# Sensor_HallArray_StandAlone_2mm.net
KiCad netlist of a schematic drawn in EAGLE
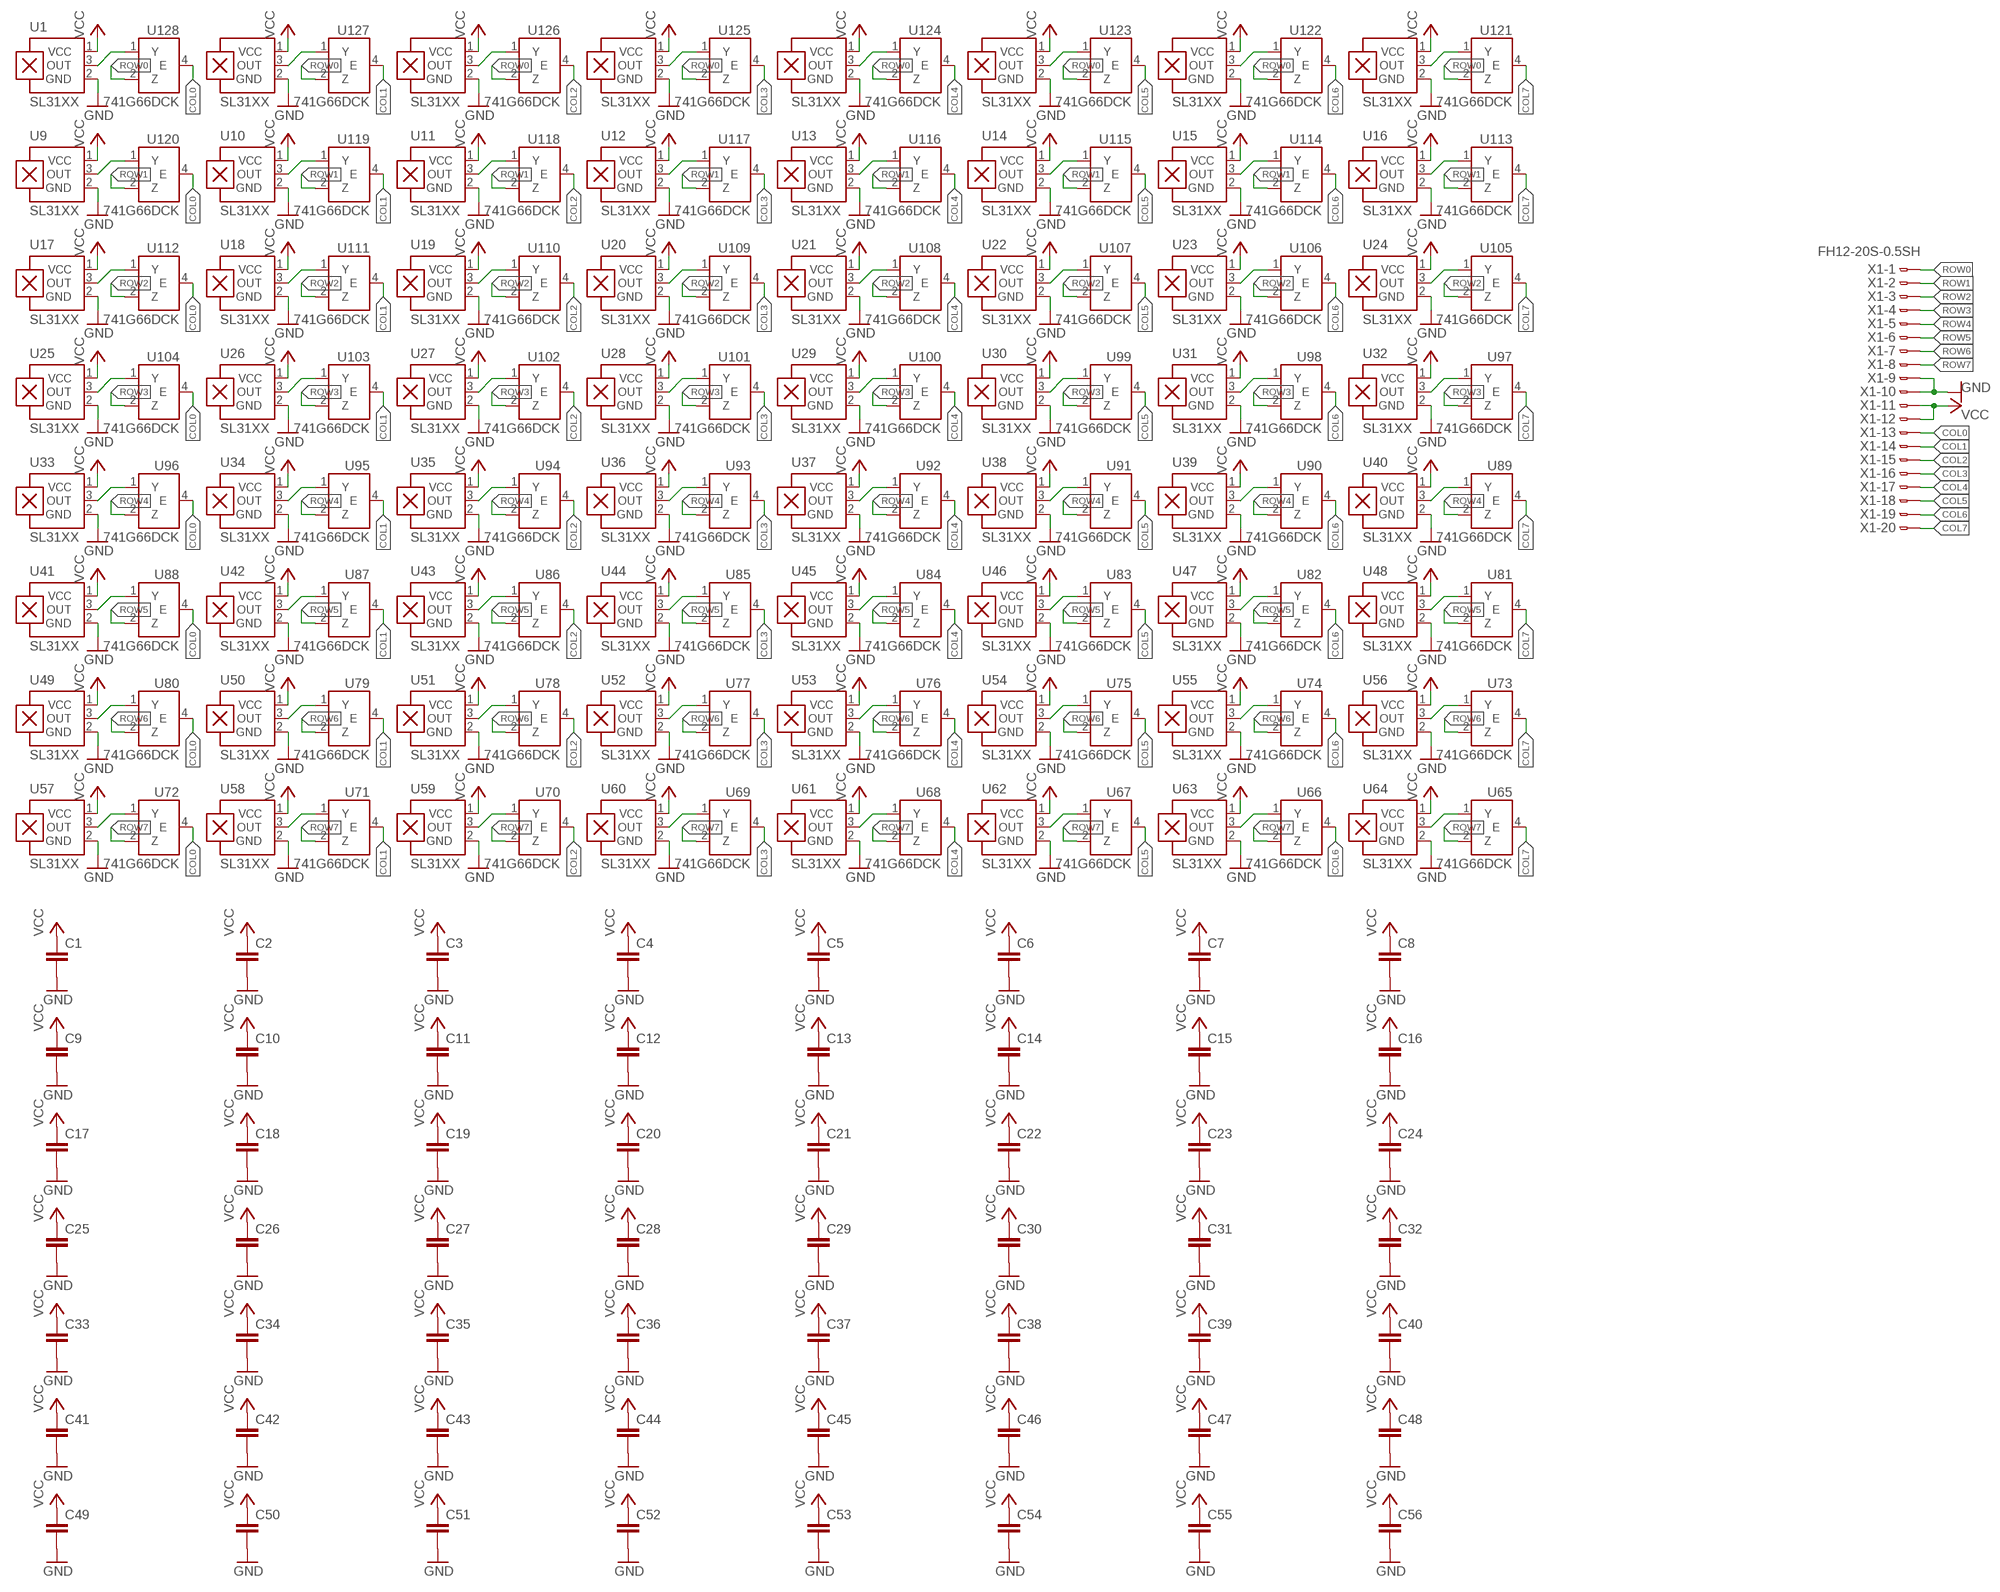
[diagram p0: schematic, sheet 1]

(export (version "E")
  (design (tool "Eeschema 10.0.6"))
  (components
    (comp (ref "C1")
      (value "C-EUC0201")
      (footprint "eagle-import:C0201")
      (libsource (lib "eagle-import") (part "C-EUC0201"))
    )
    (comp (ref "C2")
      (value "C-EUC0201")
      (footprint "eagle-import:C0201")
      (libsource (lib "eagle-import") (part "C-EUC0201"))
    )
    (comp (ref "C3")
      (value "C-EUC0201")
      (footprint "eagle-import:C0201")
      (libsource (lib "eagle-import") (part "C-EUC0201"))
    )
    (comp (ref "C4")
      (value "C-EUC0201")
      (footprint "eagle-import:C0201")
      (libsource (lib "eagle-import") (part "C-EUC0201"))
    )
    (comp (ref "C5")
      (value "C-EUC0201")
      (footprint "eagle-import:C0201")
      (libsource (lib "eagle-import") (part "C-EUC0201"))
    )
    (comp (ref "C6")
      (value "C-EUC0201")
      (footprint "eagle-import:C0201")
      (libsource (lib "eagle-import") (part "C-EUC0201"))
    )
    (comp (ref "C7")
      (value "C-EUC0201")
      (footprint "eagle-import:C0201")
      (libsource (lib "eagle-import") (part "C-EUC0201"))
    )
    (comp (ref "C8")
      (value "C-EUC0201")
      (footprint "eagle-import:C0201")
      (libsource (lib "eagle-import") (part "C-EUC0201"))
    )
    (comp (ref "C9")
      (value "C-EUC0201")
      (footprint "eagle-import:C0201")
      (libsource (lib "eagle-import") (part "C-EUC0201"))
    )
    (comp (ref "C10")
      (value "C-EUC0201")
      (footprint "eagle-import:C0201")
      (libsource (lib "eagle-import") (part "C-EUC0201"))
    )
    (comp (ref "C11")
      (value "C-EUC0201")
      (footprint "eagle-import:C0201")
      (libsource (lib "eagle-import") (part "C-EUC0201"))
    )
    (comp (ref "C12")
      (value "C-EUC0201")
      (footprint "eagle-import:C0201")
      (libsource (lib "eagle-import") (part "C-EUC0201"))
    )
    (comp (ref "C13")
      (value "C-EUC0201")
      (footprint "eagle-import:C0201")
      (libsource (lib "eagle-import") (part "C-EUC0201"))
    )
    (comp (ref "C14")
      (value "C-EUC0201")
      (footprint "eagle-import:C0201")
      (libsource (lib "eagle-import") (part "C-EUC0201"))
    )
    (comp (ref "C15")
      (value "C-EUC0201")
      (footprint "eagle-import:C0201")
      (libsource (lib "eagle-import") (part "C-EUC0201"))
    )
    (comp (ref "C16")
      (value "C-EUC0201")
      (footprint "eagle-import:C0201")
      (libsource (lib "eagle-import") (part "C-EUC0201"))
    )
    (comp (ref "C17")
      (value "C-EUC0201")
      (footprint "eagle-import:C0201")
      (libsource (lib "eagle-import") (part "C-EUC0201"))
    )
    (comp (ref "C18")
      (value "C-EUC0201")
      (footprint "eagle-import:C0201")
      (libsource (lib "eagle-import") (part "C-EUC0201"))
    )
    (comp (ref "C19")
      (value "C-EUC0201")
      (footprint "eagle-import:C0201")
      (libsource (lib "eagle-import") (part "C-EUC0201"))
    )
    (comp (ref "C20")
      (value "C-EUC0201")
      (footprint "eagle-import:C0201")
      (libsource (lib "eagle-import") (part "C-EUC0201"))
    )
    (comp (ref "C21")
      (value "C-EUC0201")
      (footprint "eagle-import:C0201")
      (libsource (lib "eagle-import") (part "C-EUC0201"))
    )
    (comp (ref "C22")
      (value "C-EUC0201")
      (footprint "eagle-import:C0201")
      (libsource (lib "eagle-import") (part "C-EUC0201"))
    )
    (comp (ref "C23")
      (value "C-EUC0201")
      (footprint "eagle-import:C0201")
      (libsource (lib "eagle-import") (part "C-EUC0201"))
    )
    (comp (ref "C24")
      (value "C-EUC0201")
      (footprint "eagle-import:C0201")
      (libsource (lib "eagle-import") (part "C-EUC0201"))
    )
    (comp (ref "C25")
      (value "C-EUC0201")
      (footprint "eagle-import:C0201")
      (libsource (lib "eagle-import") (part "C-EUC0201"))
    )
    (comp (ref "C26")
      (value "C-EUC0201")
      (footprint "eagle-import:C0201")
      (libsource (lib "eagle-import") (part "C-EUC0201"))
    )
    (comp (ref "C27")
      (value "C-EUC0201")
      (footprint "eagle-import:C0201")
      (libsource (lib "eagle-import") (part "C-EUC0201"))
    )
    (comp (ref "C28")
      (value "C-EUC0201")
      (footprint "eagle-import:C0201")
      (libsource (lib "eagle-import") (part "C-EUC0201"))
    )
    (comp (ref "C29")
      (value "C-EUC0201")
      (footprint "eagle-import:C0201")
      (libsource (lib "eagle-import") (part "C-EUC0201"))
    )
    (comp (ref "C30")
      (value "C-EUC0201")
      (footprint "eagle-import:C0201")
      (libsource (lib "eagle-import") (part "C-EUC0201"))
    )
    (comp (ref "C31")
      (value "C-EUC0201")
      (footprint "eagle-import:C0201")
      (libsource (lib "eagle-import") (part "C-EUC0201"))
    )
    (comp (ref "C32")
      (value "C-EUC0201")
      (footprint "eagle-import:C0201")
      (libsource (lib "eagle-import") (part "C-EUC0201"))
    )
    (comp (ref "C33")
      (value "C-EUC0201")
      (footprint "eagle-import:C0201")
      (libsource (lib "eagle-import") (part "C-EUC0201"))
    )
    (comp (ref "C34")
      (value "C-EUC0201")
      (footprint "eagle-import:C0201")
      (libsource (lib "eagle-import") (part "C-EUC0201"))
    )
    (comp (ref "C35")
      (value "C-EUC0201")
      (footprint "eagle-import:C0201")
      (libsource (lib "eagle-import") (part "C-EUC0201"))
    )
    (comp (ref "C36")
      (value "C-EUC0201")
      (footprint "eagle-import:C0201")
      (libsource (lib "eagle-import") (part "C-EUC0201"))
    )
    (comp (ref "C37")
      (value "C-EUC0201")
      (footprint "eagle-import:C0201")
      (libsource (lib "eagle-import") (part "C-EUC0201"))
    )
    (comp (ref "C38")
      (value "C-EUC0201")
      (footprint "eagle-import:C0201")
      (libsource (lib "eagle-import") (part "C-EUC0201"))
    )
    (comp (ref "C39")
      (value "C-EUC0201")
      (footprint "eagle-import:C0201")
      (libsource (lib "eagle-import") (part "C-EUC0201"))
    )
    (comp (ref "C40")
      (value "C-EUC0201")
      (footprint "eagle-import:C0201")
      (libsource (lib "eagle-import") (part "C-EUC0201"))
    )
    (comp (ref "C41")
      (value "C-EUC0201")
      (footprint "eagle-import:C0201")
      (libsource (lib "eagle-import") (part "C-EUC0201"))
    )
    (comp (ref "C42")
      (value "C-EUC0201")
      (footprint "eagle-import:C0201")
      (libsource (lib "eagle-import") (part "C-EUC0201"))
    )
    (comp (ref "C43")
      (value "C-EUC0201")
      (footprint "eagle-import:C0201")
      (libsource (lib "eagle-import") (part "C-EUC0201"))
    )
    (comp (ref "C44")
      (value "C-EUC0201")
      (footprint "eagle-import:C0201")
      (libsource (lib "eagle-import") (part "C-EUC0201"))
    )
    (comp (ref "C45")
      (value "C-EUC0201")
      (footprint "eagle-import:C0201")
      (libsource (lib "eagle-import") (part "C-EUC0201"))
    )
    (comp (ref "C46")
      (value "C-EUC0201")
      (footprint "eagle-import:C0201")
      (libsource (lib "eagle-import") (part "C-EUC0201"))
    )
    (comp (ref "C47")
      (value "C-EUC0201")
      (footprint "eagle-import:C0201")
      (libsource (lib "eagle-import") (part "C-EUC0201"))
    )
    (comp (ref "C48")
      (value "C-EUC0201")
      (footprint "eagle-import:C0201")
      (libsource (lib "eagle-import") (part "C-EUC0201"))
    )
    (comp (ref "C49")
      (value "C-EUC0201")
      (footprint "eagle-import:C0201")
      (libsource (lib "eagle-import") (part "C-EUC0201"))
    )
    (comp (ref "C50")
      (value "C-EUC0201")
      (footprint "eagle-import:C0201")
      (libsource (lib "eagle-import") (part "C-EUC0201"))
    )
    (comp (ref "C51")
      (value "C-EUC0201")
      (footprint "eagle-import:C0201")
      (libsource (lib "eagle-import") (part "C-EUC0201"))
    )
    (comp (ref "C52")
      (value "C-EUC0201")
      (footprint "eagle-import:C0201")
      (libsource (lib "eagle-import") (part "C-EUC0201"))
    )
    (comp (ref "C53")
      (value "C-EUC0201")
      (footprint "eagle-import:C0201")
      (libsource (lib "eagle-import") (part "C-EUC0201"))
    )
    (comp (ref "C54")
      (value "C-EUC0201")
      (footprint "eagle-import:C0201")
      (libsource (lib "eagle-import") (part "C-EUC0201"))
    )
    (comp (ref "C55")
      (value "C-EUC0201")
      (footprint "eagle-import:C0201")
      (libsource (lib "eagle-import") (part "C-EUC0201"))
    )
    (comp (ref "C56")
      (value "C-EUC0201")
      (footprint "eagle-import:C0201")
      (libsource (lib "eagle-import") (part "C-EUC0201"))
    )
    (comp (ref "U1")
      (value "SL31XX")
      (footprint "eagle-import:SOT1215")
      (libsource (lib "eagle-import") (part "SL31XX"))
    )
    (comp (ref "U2")
      (value "SL31XX")
      (footprint "eagle-import:SOT1215")
      (libsource (lib "eagle-import") (part "SL31XX"))
    )
    (comp (ref "U3")
      (value "SL31XX")
      (footprint "eagle-import:SOT1215")
      (libsource (lib "eagle-import") (part "SL31XX"))
    )
    (comp (ref "U4")
      (value "SL31XX")
      (footprint "eagle-import:SOT1215")
      (libsource (lib "eagle-import") (part "SL31XX"))
    )
    (comp (ref "U5")
      (value "SL31XX")
      (footprint "eagle-import:SOT1215")
      (libsource (lib "eagle-import") (part "SL31XX"))
    )
    (comp (ref "U6")
      (value "SL31XX")
      (footprint "eagle-import:SOT1215")
      (libsource (lib "eagle-import") (part "SL31XX"))
    )
    (comp (ref "U7")
      (value "SL31XX")
      (footprint "eagle-import:SOT1215")
      (libsource (lib "eagle-import") (part "SL31XX"))
    )
    (comp (ref "U8")
      (value "SL31XX")
      (footprint "eagle-import:SOT1215")
      (libsource (lib "eagle-import") (part "SL31XX"))
    )
    (comp (ref "U9")
      (value "SL31XX")
      (footprint "eagle-import:SOT1215")
      (libsource (lib "eagle-import") (part "SL31XX"))
    )
    (comp (ref "U10")
      (value "SL31XX")
      (footprint "eagle-import:SOT1215")
      (libsource (lib "eagle-import") (part "SL31XX"))
    )
    (comp (ref "U11")
      (value "SL31XX")
      (footprint "eagle-import:SOT1215")
      (libsource (lib "eagle-import") (part "SL31XX"))
    )
    (comp (ref "U12")
      (value "SL31XX")
      (footprint "eagle-import:SOT1215")
      (libsource (lib "eagle-import") (part "SL31XX"))
    )
    (comp (ref "U13")
      (value "SL31XX")
      (footprint "eagle-import:SOT1215")
      (libsource (lib "eagle-import") (part "SL31XX"))
    )
    (comp (ref "U14")
      (value "SL31XX")
      (footprint "eagle-import:SOT1215")
      (libsource (lib "eagle-import") (part "SL31XX"))
    )
    (comp (ref "U15")
      (value "SL31XX")
      (footprint "eagle-import:SOT1215")
      (libsource (lib "eagle-import") (part "SL31XX"))
    )
    (comp (ref "U16")
      (value "SL31XX")
      (footprint "eagle-import:SOT1215")
      (libsource (lib "eagle-import") (part "SL31XX"))
    )
    (comp (ref "U17")
      (value "SL31XX")
      (footprint "eagle-import:SOT1215")
      (libsource (lib "eagle-import") (part "SL31XX"))
    )
    (comp (ref "U18")
      (value "SL31XX")
      (footprint "eagle-import:SOT1215")
      (libsource (lib "eagle-import") (part "SL31XX"))
    )
    (comp (ref "U19")
      (value "SL31XX")
      (footprint "eagle-import:SOT1215")
      (libsource (lib "eagle-import") (part "SL31XX"))
    )
    (comp (ref "U20")
      (value "SL31XX")
      (footprint "eagle-import:SOT1215")
      (libsource (lib "eagle-import") (part "SL31XX"))
    )
    (comp (ref "U21")
      (value "SL31XX")
      (footprint "eagle-import:SOT1215")
      (libsource (lib "eagle-import") (part "SL31XX"))
    )
    (comp (ref "U22")
      (value "SL31XX")
      (footprint "eagle-import:SOT1215")
      (libsource (lib "eagle-import") (part "SL31XX"))
    )
    (comp (ref "U23")
      (value "SL31XX")
      (footprint "eagle-import:SOT1215")
      (libsource (lib "eagle-import") (part "SL31XX"))
    )
    (comp (ref "U24")
      (value "SL31XX")
      (footprint "eagle-import:SOT1215")
      (libsource (lib "eagle-import") (part "SL31XX"))
    )
    (comp (ref "U25")
      (value "SL31XX")
      (footprint "eagle-import:SOT1215")
      (libsource (lib "eagle-import") (part "SL31XX"))
    )
    (comp (ref "U26")
      (value "SL31XX")
      (footprint "eagle-import:SOT1215")
      (libsource (lib "eagle-import") (part "SL31XX"))
    )
    (comp (ref "U27")
      (value "SL31XX")
      (footprint "eagle-import:SOT1215")
      (libsource (lib "eagle-import") (part "SL31XX"))
    )
    (comp (ref "U28")
      (value "SL31XX")
      (footprint "eagle-import:SOT1215")
      (libsource (lib "eagle-import") (part "SL31XX"))
    )
    (comp (ref "U29")
      (value "SL31XX")
      (footprint "eagle-import:SOT1215")
      (libsource (lib "eagle-import") (part "SL31XX"))
    )
    (comp (ref "U30")
      (value "SL31XX")
      (footprint "eagle-import:SOT1215")
      (libsource (lib "eagle-import") (part "SL31XX"))
    )
    (comp (ref "U31")
      (value "SL31XX")
      (footprint "eagle-import:SOT1215")
      (libsource (lib "eagle-import") (part "SL31XX"))
    )
    (comp (ref "U32")
      (value "SL31XX")
      (footprint "eagle-import:SOT1215")
      (libsource (lib "eagle-import") (part "SL31XX"))
    )
    (comp (ref "U33")
      (value "SL31XX")
      (footprint "eagle-import:SOT1215")
      (libsource (lib "eagle-import") (part "SL31XX"))
    )
    (comp (ref "U34")
      (value "SL31XX")
      (footprint "eagle-import:SOT1215")
      (libsource (lib "eagle-import") (part "SL31XX"))
    )
    (comp (ref "U35")
      (value "SL31XX")
      (footprint "eagle-import:SOT1215")
      (libsource (lib "eagle-import") (part "SL31XX"))
    )
    (comp (ref "U36")
      (value "SL31XX")
      (footprint "eagle-import:SOT1215")
      (libsource (lib "eagle-import") (part "SL31XX"))
    )
    (comp (ref "U37")
      (value "SL31XX")
      (footprint "eagle-import:SOT1215")
      (libsource (lib "eagle-import") (part "SL31XX"))
    )
    (comp (ref "U38")
      (value "SL31XX")
      (footprint "eagle-import:SOT1215")
      (libsource (lib "eagle-import") (part "SL31XX"))
    )
    (comp (ref "U39")
      (value "SL31XX")
      (footprint "eagle-import:SOT1215")
      (libsource (lib "eagle-import") (part "SL31XX"))
    )
    (comp (ref "U40")
      (value "SL31XX")
      (footprint "eagle-import:SOT1215")
      (libsource (lib "eagle-import") (part "SL31XX"))
    )
    (comp (ref "U41")
      (value "SL31XX")
      (footprint "eagle-import:SOT1215")
      (libsource (lib "eagle-import") (part "SL31XX"))
    )
    (comp (ref "U42")
      (value "SL31XX")
      (footprint "eagle-import:SOT1215")
      (libsource (lib "eagle-import") (part "SL31XX"))
    )
    (comp (ref "U43")
      (value "SL31XX")
      (footprint "eagle-import:SOT1215")
      (libsource (lib "eagle-import") (part "SL31XX"))
    )
    (comp (ref "U44")
      (value "SL31XX")
      (footprint "eagle-import:SOT1215")
      (libsource (lib "eagle-import") (part "SL31XX"))
    )
    (comp (ref "U45")
      (value "SL31XX")
      (footprint "eagle-import:SOT1215")
      (libsource (lib "eagle-import") (part "SL31XX"))
    )
    (comp (ref "U46")
      (value "SL31XX")
      (footprint "eagle-import:SOT1215")
      (libsource (lib "eagle-import") (part "SL31XX"))
    )
    (comp (ref "U47")
      (value "SL31XX")
      (footprint "eagle-import:SOT1215")
      (libsource (lib "eagle-import") (part "SL31XX"))
    )
    (comp (ref "U48")
      (value "SL31XX")
      (footprint "eagle-import:SOT1215")
      (libsource (lib "eagle-import") (part "SL31XX"))
    )
    (comp (ref "U49")
      (value "SL31XX")
      (footprint "eagle-import:SOT1215")
      (libsource (lib "eagle-import") (part "SL31XX"))
    )
    (comp (ref "U50")
      (value "SL31XX")
      (footprint "eagle-import:SOT1215")
      (libsource (lib "eagle-import") (part "SL31XX"))
    )
    (comp (ref "U51")
      (value "SL31XX")
      (footprint "eagle-import:SOT1215")
      (libsource (lib "eagle-import") (part "SL31XX"))
    )
    (comp (ref "U52")
      (value "SL31XX")
      (footprint "eagle-import:SOT1215")
      (libsource (lib "eagle-import") (part "SL31XX"))
    )
    (comp (ref "U53")
      (value "SL31XX")
      (footprint "eagle-import:SOT1215")
      (libsource (lib "eagle-import") (part "SL31XX"))
    )
    (comp (ref "U54")
      (value "SL31XX")
      (footprint "eagle-import:SOT1215")
      (libsource (lib "eagle-import") (part "SL31XX"))
    )
    (comp (ref "U55")
      (value "SL31XX")
      (footprint "eagle-import:SOT1215")
      (libsource (lib "eagle-import") (part "SL31XX"))
    )
    (comp (ref "U56")
      (value "SL31XX")
      (footprint "eagle-import:SOT1215")
      (libsource (lib "eagle-import") (part "SL31XX"))
    )
    (comp (ref "U57")
      (value "SL31XX")
      (footprint "eagle-import:SOT1215")
      (libsource (lib "eagle-import") (part "SL31XX"))
    )
    (comp (ref "U58")
      (value "SL31XX")
      (footprint "eagle-import:SOT1215")
      (libsource (lib "eagle-import") (part "SL31XX"))
    )
    (comp (ref "U59")
      (value "SL31XX")
      (footprint "eagle-import:SOT1215")
      (libsource (lib "eagle-import") (part "SL31XX"))
    )
    (comp (ref "U60")
      (value "SL31XX")
      (footprint "eagle-import:SOT1215")
      (libsource (lib "eagle-import") (part "SL31XX"))
    )
    (comp (ref "U61")
      (value "SL31XX")
      (footprint "eagle-import:SOT1215")
      (libsource (lib "eagle-import") (part "SL31XX"))
    )
    (comp (ref "U62")
      (value "SL31XX")
      (footprint "eagle-import:SOT1215")
      (libsource (lib "eagle-import") (part "SL31XX"))
    )
    (comp (ref "U63")
      (value "SL31XX")
      (footprint "eagle-import:SOT1215")
      (libsource (lib "eagle-import") (part "SL31XX"))
    )
    (comp (ref "U64")
      (value "SL31XX")
      (footprint "eagle-import:SOT1215")
      (libsource (lib "eagle-import") (part "SL31XX"))
    )
    (comp (ref "U65")
      (value "741G66DCK")
      (footprint "eagle-import:SC70-5")
      (libsource (lib "eagle-import") (part "741G66DCK"))
    )
    (comp (ref "U66")
      (value "741G66DCK")
      (footprint "eagle-import:SC70-5")
      (libsource (lib "eagle-import") (part "741G66DCK"))
    )
    (comp (ref "U67")
      (value "741G66DCK")
      (footprint "eagle-import:SC70-5")
      (libsource (lib "eagle-import") (part "741G66DCK"))
    )
    (comp (ref "U68")
      (value "741G66DCK")
      (footprint "eagle-import:SC70-5")
      (libsource (lib "eagle-import") (part "741G66DCK"))
    )
    (comp (ref "U69")
      (value "741G66DCK")
      (footprint "eagle-import:SC70-5")
      (libsource (lib "eagle-import") (part "741G66DCK"))
    )
    (comp (ref "U70")
      (value "741G66DCK")
      (footprint "eagle-import:SC70-5")
      (libsource (lib "eagle-import") (part "741G66DCK"))
    )
    (comp (ref "U71")
      (value "741G66DCK")
      (footprint "eagle-import:SC70-5")
      (libsource (lib "eagle-import") (part "741G66DCK"))
    )
    (comp (ref "U72")
      (value "741G66DCK")
      (footprint "eagle-import:SC70-5")
      (libsource (lib "eagle-import") (part "741G66DCK"))
    )
    (comp (ref "U73")
      (value "741G66DCK")
      (footprint "eagle-import:SC70-5")
      (libsource (lib "eagle-import") (part "741G66DCK"))
    )
    (comp (ref "U74")
      (value "741G66DCK")
      (footprint "eagle-import:SC70-5")
      (libsource (lib "eagle-import") (part "741G66DCK"))
    )
    (comp (ref "U75")
      (value "741G66DCK")
      (footprint "eagle-import:SC70-5")
      (libsource (lib "eagle-import") (part "741G66DCK"))
    )
    (comp (ref "U76")
      (value "741G66DCK")
      (footprint "eagle-import:SC70-5")
      (libsource (lib "eagle-import") (part "741G66DCK"))
    )
    (comp (ref "U77")
      (value "741G66DCK")
      (footprint "eagle-import:SC70-5")
      (libsource (lib "eagle-import") (part "741G66DCK"))
    )
    (comp (ref "U78")
      (value "741G66DCK")
      (footprint "eagle-import:SC70-5")
      (libsource (lib "eagle-import") (part "741G66DCK"))
    )
    (comp (ref "U79")
      (value "741G66DCK")
      (footprint "eagle-import:SC70-5")
      (libsource (lib "eagle-import") (part "741G66DCK"))
    )
    (comp (ref "U80")
      (value "741G66DCK")
      (footprint "eagle-import:SC70-5")
      (libsource (lib "eagle-import") (part "741G66DCK"))
    )
    (comp (ref "U81")
      (value "741G66DCK")
      (footprint "eagle-import:SC70-5")
      (libsource (lib "eagle-import") (part "741G66DCK"))
    )
    (comp (ref "U82")
      (value "741G66DCK")
      (footprint "eagle-import:SC70-5")
      (libsource (lib "eagle-import") (part "741G66DCK"))
    )
    (comp (ref "U83")
      (value "741G66DCK")
      (footprint "eagle-import:SC70-5")
      (libsource (lib "eagle-import") (part "741G66DCK"))
    )
    (comp (ref "U84")
      (value "741G66DCK")
      (footprint "eagle-import:SC70-5")
      (libsource (lib "eagle-import") (part "741G66DCK"))
    )
    (comp (ref "U85")
      (value "741G66DCK")
      (footprint "eagle-import:SC70-5")
      (libsource (lib "eagle-import") (part "741G66DCK"))
    )
    (comp (ref "U86")
      (value "741G66DCK")
      (footprint "eagle-import:SC70-5")
      (libsource (lib "eagle-import") (part "741G66DCK"))
    )
    (comp (ref "U87")
      (value "741G66DCK")
      (footprint "eagle-import:SC70-5")
      (libsource (lib "eagle-import") (part "741G66DCK"))
    )
    (comp (ref "U88")
      (value "741G66DCK")
      (footprint "eagle-import:SC70-5")
      (libsource (lib "eagle-import") (part "741G66DCK"))
    )
    (comp (ref "U89")
      (value "741G66DCK")
      (footprint "eagle-import:SC70-5")
      (libsource (lib "eagle-import") (part "741G66DCK"))
    )
    (comp (ref "U90")
      (value "741G66DCK")
      (footprint "eagle-import:SC70-5")
      (libsource (lib "eagle-import") (part "741G66DCK"))
    )
    (comp (ref "U91")
      (value "741G66DCK")
      (footprint "eagle-import:SC70-5")
      (libsource (lib "eagle-import") (part "741G66DCK"))
    )
    (comp (ref "U92")
      (value "741G66DCK")
      (footprint "eagle-import:SC70-5")
      (libsource (lib "eagle-import") (part "741G66DCK"))
    )
    (comp (ref "U93")
      (value "741G66DCK")
      (footprint "eagle-import:SC70-5")
      (libsource (lib "eagle-import") (part "741G66DCK"))
    )
    (comp (ref "U94")
      (value "741G66DCK")
      (footprint "eagle-import:SC70-5")
      (libsource (lib "eagle-import") (part "741G66DCK"))
    )
    (comp (ref "U95")
      (value "741G66DCK")
      (footprint "eagle-import:SC70-5")
      (libsource (lib "eagle-import") (part "741G66DCK"))
    )
    (comp (ref "U96")
      (value "741G66DCK")
      (footprint "eagle-import:SC70-5")
      (libsource (lib "eagle-import") (part "741G66DCK"))
    )
    (comp (ref "U97")
      (value "741G66DCK")
      (footprint "eagle-import:SC70-5")
      (libsource (lib "eagle-import") (part "741G66DCK"))
    )
    (comp (ref "U98")
      (value "741G66DCK")
      (footprint "eagle-import:SC70-5")
      (libsource (lib "eagle-import") (part "741G66DCK"))
    )
    (comp (ref "U99")
      (value "741G66DCK")
      (footprint "eagle-import:SC70-5")
      (libsource (lib "eagle-import") (part "741G66DCK"))
    )
    (comp (ref "U100")
      (value "741G66DCK")
      (footprint "eagle-import:SC70-5")
      (libsource (lib "eagle-import") (part "741G66DCK"))
    )
    (comp (ref "U101")
      (value "741G66DCK")
      (footprint "eagle-import:SC70-5")
      (libsource (lib "eagle-import") (part "741G66DCK"))
    )
    (comp (ref "U102")
      (value "741G66DCK")
      (footprint "eagle-import:SC70-5")
      (libsource (lib "eagle-import") (part "741G66DCK"))
    )
    (comp (ref "U103")
      (value "741G66DCK")
      (footprint "eagle-import:SC70-5")
      (libsource (lib "eagle-import") (part "741G66DCK"))
    )
    (comp (ref "U104")
      (value "741G66DCK")
      (footprint "eagle-import:SC70-5")
      (libsource (lib "eagle-import") (part "741G66DCK"))
    )
    (comp (ref "U105")
      (value "741G66DCK")
      (footprint "eagle-import:SC70-5")
      (libsource (lib "eagle-import") (part "741G66DCK"))
    )
    (comp (ref "U106")
      (value "741G66DCK")
      (footprint "eagle-import:SC70-5")
      (libsource (lib "eagle-import") (part "741G66DCK"))
    )
    (comp (ref "U107")
      (value "741G66DCK")
      (footprint "eagle-import:SC70-5")
      (libsource (lib "eagle-import") (part "741G66DCK"))
    )
    (comp (ref "U108")
      (value "741G66DCK")
      (footprint "eagle-import:SC70-5")
      (libsource (lib "eagle-import") (part "741G66DCK"))
    )
    (comp (ref "U109")
      (value "741G66DCK")
      (footprint "eagle-import:SC70-5")
      (libsource (lib "eagle-import") (part "741G66DCK"))
    )
    (comp (ref "U110")
      (value "741G66DCK")
      (footprint "eagle-import:SC70-5")
      (libsource (lib "eagle-import") (part "741G66DCK"))
    )
    (comp (ref "U111")
      (value "741G66DCK")
      (footprint "eagle-import:SC70-5")
      (libsource (lib "eagle-import") (part "741G66DCK"))
    )
    (comp (ref "U112")
      (value "741G66DCK")
      (footprint "eagle-import:SC70-5")
      (libsource (lib "eagle-import") (part "741G66DCK"))
    )
    (comp (ref "U113")
      (value "741G66DCK")
      (footprint "eagle-import:SC70-5")
      (libsource (lib "eagle-import") (part "741G66DCK"))
    )
    (comp (ref "U114")
      (value "741G66DCK")
      (footprint "eagle-import:SC70-5")
      (libsource (lib "eagle-import") (part "741G66DCK"))
    )
    (comp (ref "U115")
      (value "741G66DCK")
      (footprint "eagle-import:SC70-5")
      (libsource (lib "eagle-import") (part "741G66DCK"))
    )
    (comp (ref "U116")
      (value "741G66DCK")
      (footprint "eagle-import:SC70-5")
      (libsource (lib "eagle-import") (part "741G66DCK"))
    )
    (comp (ref "U117")
      (value "741G66DCK")
      (footprint "eagle-import:SC70-5")
      (libsource (lib "eagle-import") (part "741G66DCK"))
    )
    (comp (ref "U118")
      (value "741G66DCK")
      (footprint "eagle-import:SC70-5")
      (libsource (lib "eagle-import") (part "741G66DCK"))
    )
    (comp (ref "U119")
      (value "741G66DCK")
      (footprint "eagle-import:SC70-5")
      (libsource (lib "eagle-import") (part "741G66DCK"))
    )
    (comp (ref "U120")
      (value "741G66DCK")
      (footprint "eagle-import:SC70-5")
      (libsource (lib "eagle-import") (part "741G66DCK"))
    )
    (comp (ref "U121")
      (value "741G66DCK")
      (footprint "eagle-import:SC70-5")
      (libsource (lib "eagle-import") (part "741G66DCK"))
    )
    (comp (ref "U122")
      (value "741G66DCK")
      (footprint "eagle-import:SC70-5")
      (libsource (lib "eagle-import") (part "741G66DCK"))
    )
    (comp (ref "U123")
      (value "741G66DCK")
      (footprint "eagle-import:SC70-5")
      (libsource (lib "eagle-import") (part "741G66DCK"))
    )
    (comp (ref "U124")
      (value "741G66DCK")
      (footprint "eagle-import:SC70-5")
      (libsource (lib "eagle-import") (part "741G66DCK"))
    )
    (comp (ref "U125")
      (value "741G66DCK")
      (footprint "eagle-import:SC70-5")
      (libsource (lib "eagle-import") (part "741G66DCK"))
    )
    (comp (ref "U126")
      (value "741G66DCK")
      (footprint "eagle-import:SC70-5")
      (libsource (lib "eagle-import") (part "741G66DCK"))
    )
    (comp (ref "U127")
      (value "741G66DCK")
      (footprint "eagle-import:SC70-5")
      (libsource (lib "eagle-import") (part "741G66DCK"))
    )
    (comp (ref "U128")
      (value "741G66DCK")
      (footprint "eagle-import:SC70-5")
      (libsource (lib "eagle-import") (part "741G66DCK"))
    )
    (comp (ref "X1")
      (value "FH12-20S-0.5SH")
      (footprint "eagle-import:FH12-20S-0.5SH")
      (fields (field (name "MPN") "FH12-20S-0.5SH(55)"))
      (libsource (lib "eagle-import") (part "FH12-20S-0.5SH"))
    )
  )
  (nets
    (net (code "1") (name "COL0") (class "Default")
      (node (ref "U104") (pin "4") (pinfunction "E_4") (pintype "input"))
      (node (ref "U112") (pin "4") (pinfunction "E_4") (pintype "input"))
      (node (ref "U120") (pin "4") (pinfunction "E_4") (pintype "input"))
      (node (ref "U128") (pin "4") (pinfunction "E_4") (pintype "input"))
      (node (ref "U72") (pin "4") (pinfunction "E_4") (pintype "input"))
      (node (ref "U80") (pin "4") (pinfunction "E_4") (pintype "input"))
      (node (ref "U88") (pin "4") (pinfunction "E_4") (pintype "input"))
      (node (ref "U96") (pin "4") (pinfunction "E_4") (pintype "input"))
      (node (ref "X1") (pin "13") (pinfunction "1_13") (pintype "passive"))
    )
    (net (code "2") (name "COL1") (class "Default")
      (node (ref "U103") (pin "4") (pinfunction "E_4") (pintype "input"))
      (node (ref "U111") (pin "4") (pinfunction "E_4") (pintype "input"))
      (node (ref "U119") (pin "4") (pinfunction "E_4") (pintype "input"))
      (node (ref "U127") (pin "4") (pinfunction "E_4") (pintype "input"))
      (node (ref "U71") (pin "4") (pinfunction "E_4") (pintype "input"))
      (node (ref "U79") (pin "4") (pinfunction "E_4") (pintype "input"))
      (node (ref "U87") (pin "4") (pinfunction "E_4") (pintype "input"))
      (node (ref "U95") (pin "4") (pinfunction "E_4") (pintype "input"))
      (node (ref "X1") (pin "14") (pinfunction "1_14") (pintype "passive"))
    )
    (net (code "3") (name "COL2") (class "Default")
      (node (ref "U102") (pin "4") (pinfunction "E_4") (pintype "input"))
      (node (ref "U110") (pin "4") (pinfunction "E_4") (pintype "input"))
      (node (ref "U118") (pin "4") (pinfunction "E_4") (pintype "input"))
      (node (ref "U126") (pin "4") (pinfunction "E_4") (pintype "input"))
      (node (ref "U70") (pin "4") (pinfunction "E_4") (pintype "input"))
      (node (ref "U78") (pin "4") (pinfunction "E_4") (pintype "input"))
      (node (ref "U86") (pin "4") (pinfunction "E_4") (pintype "input"))
      (node (ref "U94") (pin "4") (pinfunction "E_4") (pintype "input"))
      (node (ref "X1") (pin "15") (pinfunction "1_15") (pintype "passive"))
    )
    (net (code "4") (name "COL3") (class "Default")
      (node (ref "U101") (pin "4") (pinfunction "E_4") (pintype "input"))
      (node (ref "U109") (pin "4") (pinfunction "E_4") (pintype "input"))
      (node (ref "U117") (pin "4") (pinfunction "E_4") (pintype "input"))
      (node (ref "U125") (pin "4") (pinfunction "E_4") (pintype "input"))
      (node (ref "U69") (pin "4") (pinfunction "E_4") (pintype "input"))
      (node (ref "U77") (pin "4") (pinfunction "E_4") (pintype "input"))
      (node (ref "U85") (pin "4") (pinfunction "E_4") (pintype "input"))
      (node (ref "U93") (pin "4") (pinfunction "E_4") (pintype "input"))
      (node (ref "X1") (pin "16") (pinfunction "1_16") (pintype "passive"))
    )
    (net (code "5") (name "COL4") (class "Default")
      (node (ref "U100") (pin "4") (pinfunction "E_4") (pintype "input"))
      (node (ref "U108") (pin "4") (pinfunction "E_4") (pintype "input"))
      (node (ref "U116") (pin "4") (pinfunction "E_4") (pintype "input"))
      (node (ref "U124") (pin "4") (pinfunction "E_4") (pintype "input"))
      (node (ref "U68") (pin "4") (pinfunction "E_4") (pintype "input"))
      (node (ref "U76") (pin "4") (pinfunction "E_4") (pintype "input"))
      (node (ref "U84") (pin "4") (pinfunction "E_4") (pintype "input"))
      (node (ref "U92") (pin "4") (pinfunction "E_4") (pintype "input"))
      (node (ref "X1") (pin "17") (pinfunction "1_17") (pintype "passive"))
    )
    (net (code "6") (name "COL5") (class "Default")
      (node (ref "U107") (pin "4") (pinfunction "E_4") (pintype "input"))
      (node (ref "U115") (pin "4") (pinfunction "E_4") (pintype "input"))
      (node (ref "U123") (pin "4") (pinfunction "E_4") (pintype "input"))
      (node (ref "U67") (pin "4") (pinfunction "E_4") (pintype "input"))
      (node (ref "U75") (pin "4") (pinfunction "E_4") (pintype "input"))
      (node (ref "U83") (pin "4") (pinfunction "E_4") (pintype "input"))
      (node (ref "U91") (pin "4") (pinfunction "E_4") (pintype "input"))
      (node (ref "U99") (pin "4") (pinfunction "E_4") (pintype "input"))
      (node (ref "X1") (pin "18") (pinfunction "1_18") (pintype "passive"))
    )
    (net (code "7") (name "COL6") (class "Default")
      (node (ref "U106") (pin "4") (pinfunction "E_4") (pintype "input"))
      (node (ref "U114") (pin "4") (pinfunction "E_4") (pintype "input"))
      (node (ref "U122") (pin "4") (pinfunction "E_4") (pintype "input"))
      (node (ref "U66") (pin "4") (pinfunction "E_4") (pintype "input"))
      (node (ref "U74") (pin "4") (pinfunction "E_4") (pintype "input"))
      (node (ref "U82") (pin "4") (pinfunction "E_4") (pintype "input"))
      (node (ref "U90") (pin "4") (pinfunction "E_4") (pintype "input"))
      (node (ref "U98") (pin "4") (pinfunction "E_4") (pintype "input"))
      (node (ref "X1") (pin "19") (pinfunction "1_19") (pintype "passive"))
    )
    (net (code "8") (name "COL7") (class "Default")
      (node (ref "U105") (pin "4") (pinfunction "E_4") (pintype "input"))
      (node (ref "U113") (pin "4") (pinfunction "E_4") (pintype "input"))
      (node (ref "U121") (pin "4") (pinfunction "E_4") (pintype "input"))
      (node (ref "U65") (pin "4") (pinfunction "E_4") (pintype "input"))
      (node (ref "U73") (pin "4") (pinfunction "E_4") (pintype "input"))
      (node (ref "U81") (pin "4") (pinfunction "E_4") (pintype "input"))
      (node (ref "U89") (pin "4") (pinfunction "E_4") (pintype "input"))
      (node (ref "U97") (pin "4") (pinfunction "E_4") (pintype "input"))
      (node (ref "X1") (pin "20") (pinfunction "1_20") (pintype "passive"))
    )
    (net (code "9") (name "GND") (class "Default")
      (node (ref "C1") (pin "2") (pinfunction "2_2") (pintype "passive"))
      (node (ref "C10") (pin "2") (pinfunction "2_2") (pintype "passive"))
      (node (ref "C11") (pin "2") (pinfunction "2_2") (pintype "passive"))
      (node (ref "C12") (pin "2") (pinfunction "2_2") (pintype "passive"))
      (node (ref "C13") (pin "2") (pinfunction "2_2") (pintype "passive"))
      (node (ref "C14") (pin "2") (pinfunction "2_2") (pintype "passive"))
      (node (ref "C15") (pin "2") (pinfunction "2_2") (pintype "passive"))
      (node (ref "C16") (pin "2") (pinfunction "2_2") (pintype "passive"))
      (node (ref "C17") (pin "2") (pinfunction "2_2") (pintype "passive"))
      (node (ref "C18") (pin "2") (pinfunction "2_2") (pintype "passive"))
      (node (ref "C19") (pin "2") (pinfunction "2_2") (pintype "passive"))
      (node (ref "C2") (pin "2") (pinfunction "2_2") (pintype "passive"))
      (node (ref "C20") (pin "2") (pinfunction "2_2") (pintype "passive"))
      (node (ref "C21") (pin "2") (pinfunction "2_2") (pintype "passive"))
      (node (ref "C22") (pin "2") (pinfunction "2_2") (pintype "passive"))
      (node (ref "C23") (pin "2") (pinfunction "2_2") (pintype "passive"))
      (node (ref "C24") (pin "2") (pinfunction "2_2") (pintype "passive"))
      (node (ref "C25") (pin "2") (pinfunction "2_2") (pintype "passive"))
      (node (ref "C26") (pin "2") (pinfunction "2_2") (pintype "passive"))
      (node (ref "C27") (pin "2") (pinfunction "2_2") (pintype "passive"))
      (node (ref "C28") (pin "2") (pinfunction "2_2") (pintype "passive"))
      (node (ref "C29") (pin "2") (pinfunction "2_2") (pintype "passive"))
      (node (ref "C3") (pin "2") (pinfunction "2_2") (pintype "passive"))
      (node (ref "C30") (pin "2") (pinfunction "2_2") (pintype "passive"))
      (node (ref "C31") (pin "2") (pinfunction "2_2") (pintype "passive"))
      (node (ref "C32") (pin "2") (pinfunction "2_2") (pintype "passive"))
      (node (ref "C33") (pin "2") (pinfunction "2_2") (pintype "passive"))
      (node (ref "C34") (pin "2") (pinfunction "2_2") (pintype "passive"))
      (node (ref "C35") (pin "2") (pinfunction "2_2") (pintype "passive"))
      (node (ref "C36") (pin "2") (pinfunction "2_2") (pintype "passive"))
      (node (ref "C37") (pin "2") (pinfunction "2_2") (pintype "passive"))
      (node (ref "C38") (pin "2") (pinfunction "2_2") (pintype "passive"))
      (node (ref "C39") (pin "2") (pinfunction "2_2") (pintype "passive"))
      (node (ref "C4") (pin "2") (pinfunction "2_2") (pintype "passive"))
      (node (ref "C40") (pin "2") (pinfunction "2_2") (pintype "passive"))
      (node (ref "C41") (pin "2") (pinfunction "2_2") (pintype "passive"))
      (node (ref "C42") (pin "2") (pinfunction "2_2") (pintype "passive"))
      (node (ref "C43") (pin "2") (pinfunction "2_2") (pintype "passive"))
      (node (ref "C44") (pin "2") (pinfunction "2_2") (pintype "passive"))
      (node (ref "C45") (pin "2") (pinfunction "2_2") (pintype "passive"))
      (node (ref "C46") (pin "2") (pinfunction "2_2") (pintype "passive"))
      (node (ref "C47") (pin "2") (pinfunction "2_2") (pintype "passive"))
      (node (ref "C48") (pin "2") (pinfunction "2_2") (pintype "passive"))
      (node (ref "C49") (pin "2") (pinfunction "2_2") (pintype "passive"))
      (node (ref "C5") (pin "2") (pinfunction "2_2") (pintype "passive"))
      (node (ref "C50") (pin "2") (pinfunction "2_2") (pintype "passive"))
      (node (ref "C51") (pin "2") (pinfunction "2_2") (pintype "passive"))
      (node (ref "C52") (pin "2") (pinfunction "2_2") (pintype "passive"))
      (node (ref "C53") (pin "2") (pinfunction "2_2") (pintype "passive"))
      (node (ref "C54") (pin "2") (pinfunction "2_2") (pintype "passive"))
      (node (ref "C55") (pin "2") (pinfunction "2_2") (pintype "passive"))
      (node (ref "C56") (pin "2") (pinfunction "2_2") (pintype "passive"))
      (node (ref "C6") (pin "2") (pinfunction "2_2") (pintype "passive"))
      (node (ref "C7") (pin "2") (pinfunction "2_2") (pintype "passive"))
      (node (ref "C8") (pin "2") (pinfunction "2_2") (pintype "passive"))
      (node (ref "C9") (pin "2") (pinfunction "2_2") (pintype "passive"))
      (node (ref "U1") (pin "2") (pinfunction "GND_2") (pintype "power_in"))
      (node (ref "U10") (pin "2") (pinfunction "GND_2") (pintype "power_in"))
      (node (ref "U11") (pin "2") (pinfunction "GND_2") (pintype "power_in"))
      (node (ref "U12") (pin "2") (pinfunction "GND_2") (pintype "power_in"))
      (node (ref "U13") (pin "2") (pinfunction "GND_2") (pintype "power_in"))
      (node (ref "U14") (pin "2") (pinfunction "GND_2") (pintype "power_in"))
      (node (ref "U15") (pin "2") (pinfunction "GND_2") (pintype "power_in"))
      (node (ref "U16") (pin "2") (pinfunction "GND_2") (pintype "power_in"))
      (node (ref "U17") (pin "2") (pinfunction "GND_2") (pintype "power_in"))
      (node (ref "U18") (pin "2") (pinfunction "GND_2") (pintype "power_in"))
      (node (ref "U19") (pin "2") (pinfunction "GND_2") (pintype "power_in"))
      (node (ref "U2") (pin "2") (pinfunction "GND_2") (pintype "power_in"))
      (node (ref "U20") (pin "2") (pinfunction "GND_2") (pintype "power_in"))
      (node (ref "U21") (pin "2") (pinfunction "GND_2") (pintype "power_in"))
      (node (ref "U22") (pin "2") (pinfunction "GND_2") (pintype "power_in"))
      (node (ref "U23") (pin "2") (pinfunction "GND_2") (pintype "power_in"))
      (node (ref "U24") (pin "2") (pinfunction "GND_2") (pintype "power_in"))
      (node (ref "U25") (pin "2") (pinfunction "GND_2") (pintype "power_in"))
      (node (ref "U26") (pin "2") (pinfunction "GND_2") (pintype "power_in"))
      (node (ref "U27") (pin "2") (pinfunction "GND_2") (pintype "power_in"))
      (node (ref "U28") (pin "2") (pinfunction "GND_2") (pintype "power_in"))
      (node (ref "U29") (pin "2") (pinfunction "GND_2") (pintype "power_in"))
      (node (ref "U3") (pin "2") (pinfunction "GND_2") (pintype "power_in"))
      (node (ref "U30") (pin "2") (pinfunction "GND_2") (pintype "power_in"))
      (node (ref "U31") (pin "2") (pinfunction "GND_2") (pintype "power_in"))
      (node (ref "U32") (pin "2") (pinfunction "GND_2") (pintype "power_in"))
      (node (ref "U33") (pin "2") (pinfunction "GND_2") (pintype "power_in"))
      (node (ref "U34") (pin "2") (pinfunction "GND_2") (pintype "power_in"))
      (node (ref "U35") (pin "2") (pinfunction "GND_2") (pintype "power_in"))
      (node (ref "U36") (pin "2") (pinfunction "GND_2") (pintype "power_in"))
      (node (ref "U37") (pin "2") (pinfunction "GND_2") (pintype "power_in"))
      (node (ref "U38") (pin "2") (pinfunction "GND_2") (pintype "power_in"))
      (node (ref "U39") (pin "2") (pinfunction "GND_2") (pintype "power_in"))
      (node (ref "U4") (pin "2") (pinfunction "GND_2") (pintype "power_in"))
      (node (ref "U40") (pin "2") (pinfunction "GND_2") (pintype "power_in"))
      (node (ref "U41") (pin "2") (pinfunction "GND_2") (pintype "power_in"))
      (node (ref "U42") (pin "2") (pinfunction "GND_2") (pintype "power_in"))
      (node (ref "U43") (pin "2") (pinfunction "GND_2") (pintype "power_in"))
      (node (ref "U44") (pin "2") (pinfunction "GND_2") (pintype "power_in"))
      (node (ref "U45") (pin "2") (pinfunction "GND_2") (pintype "power_in"))
      (node (ref "U46") (pin "2") (pinfunction "GND_2") (pintype "power_in"))
      (node (ref "U47") (pin "2") (pinfunction "GND_2") (pintype "power_in"))
      (node (ref "U48") (pin "2") (pinfunction "GND_2") (pintype "power_in"))
      (node (ref "U49") (pin "2") (pinfunction "GND_2") (pintype "power_in"))
      (node (ref "U5") (pin "2") (pinfunction "GND_2") (pintype "power_in"))
      (node (ref "U50") (pin "2") (pinfunction "GND_2") (pintype "power_in"))
      (node (ref "U51") (pin "2") (pinfunction "GND_2") (pintype "power_in"))
      (node (ref "U52") (pin "2") (pinfunction "GND_2") (pintype "power_in"))
      (node (ref "U53") (pin "2") (pinfunction "GND_2") (pintype "power_in"))
      (node (ref "U54") (pin "2") (pinfunction "GND_2") (pintype "power_in"))
      (node (ref "U55") (pin "2") (pinfunction "GND_2") (pintype "power_in"))
      (node (ref "U56") (pin "2") (pinfunction "GND_2") (pintype "power_in"))
      (node (ref "U57") (pin "2") (pinfunction "GND_2") (pintype "power_in"))
      (node (ref "U58") (pin "2") (pinfunction "GND_2") (pintype "power_in"))
      (node (ref "U59") (pin "2") (pinfunction "GND_2") (pintype "power_in"))
      (node (ref "U6") (pin "2") (pinfunction "GND_2") (pintype "power_in"))
      (node (ref "U60") (pin "2") (pinfunction "GND_2") (pintype "power_in"))
      (node (ref "U61") (pin "2") (pinfunction "GND_2") (pintype "power_in"))
      (node (ref "U62") (pin "2") (pinfunction "GND_2") (pintype "power_in"))
      (node (ref "U63") (pin "2") (pinfunction "GND_2") (pintype "power_in"))
      (node (ref "U64") (pin "2") (pinfunction "GND_2") (pintype "power_in"))
      (node (ref "U7") (pin "2") (pinfunction "GND_2") (pintype "power_in"))
      (node (ref "U8") (pin "2") (pinfunction "GND_2") (pintype "power_in"))
      (node (ref "U9") (pin "2") (pinfunction "GND_2") (pintype "power_in"))
      (node (ref "X1") (pin "10") (pinfunction "1_10") (pintype "passive"))
      (node (ref "X1") (pin "9") (pinfunction "1_9") (pintype "passive"))
    )
    (net (code "10") (name "Net-(U1-OUT)") (class "Default")
      (node (ref "U1") (pin "3") (pinfunction "OUT_3") (pintype "output"))
      (node (ref "U128") (pin "1") (pinfunction "Y_1") (pintype "bidirectional"))
    )
    (net (code "11") (name "Net-(U10-OUT)") (class "Default")
      (node (ref "U10") (pin "3") (pinfunction "OUT_3") (pintype "output"))
      (node (ref "U119") (pin "1") (pinfunction "Y_1") (pintype "bidirectional"))
    )
    (net (code "12") (name "Net-(U11-OUT)") (class "Default")
      (node (ref "U11") (pin "3") (pinfunction "OUT_3") (pintype "output"))
      (node (ref "U118") (pin "1") (pinfunction "Y_1") (pintype "bidirectional"))
    )
    (net (code "13") (name "Net-(U30-OUT)") (class "Default")
      (node (ref "U30") (pin "3") (pinfunction "OUT_3") (pintype "output"))
      (node (ref "U99") (pin "1") (pinfunction "Y_1") (pintype "bidirectional"))
    )
    (net (code "14") (name "Net-(U31-OUT)") (class "Default")
      (node (ref "U31") (pin "3") (pinfunction "OUT_3") (pintype "output"))
      (node (ref "U98") (pin "1") (pinfunction "Y_1") (pintype "bidirectional"))
    )
    (net (code "15") (name "Net-(U32-OUT)") (class "Default")
      (node (ref "U32") (pin "3") (pinfunction "OUT_3") (pintype "output"))
      (node (ref "U97") (pin "1") (pinfunction "Y_1") (pintype "bidirectional"))
    )
    (net (code "16") (name "Net-(U33-OUT)") (class "Default")
      (node (ref "U33") (pin "3") (pinfunction "OUT_3") (pintype "output"))
      (node (ref "U96") (pin "1") (pinfunction "Y_1") (pintype "bidirectional"))
    )
    (net (code "17") (name "Net-(U34-OUT)") (class "Default")
      (node (ref "U34") (pin "3") (pinfunction "OUT_3") (pintype "output"))
      (node (ref "U95") (pin "1") (pinfunction "Y_1") (pintype "bidirectional"))
    )
    (net (code "18") (name "Net-(U35-OUT)") (class "Default")
      (node (ref "U35") (pin "3") (pinfunction "OUT_3") (pintype "output"))
      (node (ref "U94") (pin "1") (pinfunction "Y_1") (pintype "bidirectional"))
    )
    (net (code "19") (name "Net-(U36-OUT)") (class "Default")
      (node (ref "U36") (pin "3") (pinfunction "OUT_3") (pintype "output"))
      (node (ref "U93") (pin "1") (pinfunction "Y_1") (pintype "bidirectional"))
    )
    (net (code "20") (name "Net-(U37-OUT)") (class "Default")
      (node (ref "U37") (pin "3") (pinfunction "OUT_3") (pintype "output"))
      (node (ref "U92") (pin "1") (pinfunction "Y_1") (pintype "bidirectional"))
    )
    (net (code "21") (name "Net-(U38-OUT)") (class "Default")
      (node (ref "U38") (pin "3") (pinfunction "OUT_3") (pintype "output"))
      (node (ref "U91") (pin "1") (pinfunction "Y_1") (pintype "bidirectional"))
    )
    (net (code "22") (name "Net-(U39-OUT)") (class "Default")
      (node (ref "U39") (pin "3") (pinfunction "OUT_3") (pintype "output"))
      (node (ref "U90") (pin "1") (pinfunction "Y_1") (pintype "bidirectional"))
    )
    (net (code "23") (name "Net-(U40-OUT)") (class "Default")
      (node (ref "U40") (pin "3") (pinfunction "OUT_3") (pintype "output"))
      (node (ref "U89") (pin "1") (pinfunction "Y_1") (pintype "bidirectional"))
    )
    (net (code "24") (name "Net-(U41-OUT)") (class "Default")
      (node (ref "U41") (pin "3") (pinfunction "OUT_3") (pintype "output"))
      (node (ref "U88") (pin "1") (pinfunction "Y_1") (pintype "bidirectional"))
    )
    (net (code "25") (name "Net-(U42-OUT)") (class "Default")
      (node (ref "U42") (pin "3") (pinfunction "OUT_3") (pintype "output"))
      (node (ref "U87") (pin "1") (pinfunction "Y_1") (pintype "bidirectional"))
    )
    (net (code "26") (name "Net-(U43-OUT)") (class "Default")
      (node (ref "U43") (pin "3") (pinfunction "OUT_3") (pintype "output"))
      (node (ref "U86") (pin "1") (pinfunction "Y_1") (pintype "bidirectional"))
    )
    (net (code "27") (name "Net-(U44-OUT)") (class "Default")
      (node (ref "U44") (pin "3") (pinfunction "OUT_3") (pintype "output"))
      (node (ref "U85") (pin "1") (pinfunction "Y_1") (pintype "bidirectional"))
    )
    (net (code "28") (name "Net-(U45-OUT)") (class "Default")
      (node (ref "U45") (pin "3") (pinfunction "OUT_3") (pintype "output"))
      (node (ref "U84") (pin "1") (pinfunction "Y_1") (pintype "bidirectional"))
    )
    (net (code "29") (name "Net-(U46-OUT)") (class "Default")
      (node (ref "U46") (pin "3") (pinfunction "OUT_3") (pintype "output"))
      (node (ref "U83") (pin "1") (pinfunction "Y_1") (pintype "bidirectional"))
    )
    (net (code "30") (name "Net-(U47-OUT)") (class "Default")
      (node (ref "U47") (pin "3") (pinfunction "OUT_3") (pintype "output"))
      (node (ref "U82") (pin "1") (pinfunction "Y_1") (pintype "bidirectional"))
    )
    (net (code "31") (name "Net-(U48-OUT)") (class "Default")
      (node (ref "U48") (pin "3") (pinfunction "OUT_3") (pintype "output"))
      (node (ref "U81") (pin "1") (pinfunction "Y_1") (pintype "bidirectional"))
    )
    (net (code "32") (name "Net-(U49-OUT)") (class "Default")
      (node (ref "U49") (pin "3") (pinfunction "OUT_3") (pintype "output"))
      (node (ref "U80") (pin "1") (pinfunction "Y_1") (pintype "bidirectional"))
    )
    (net (code "33") (name "Net-(U50-OUT)") (class "Default")
      (node (ref "U50") (pin "3") (pinfunction "OUT_3") (pintype "output"))
      (node (ref "U79") (pin "1") (pinfunction "Y_1") (pintype "bidirectional"))
    )
    (net (code "34") (name "Net-(U51-OUT)") (class "Default")
      (node (ref "U51") (pin "3") (pinfunction "OUT_3") (pintype "output"))
      (node (ref "U78") (pin "1") (pinfunction "Y_1") (pintype "bidirectional"))
    )
    (net (code "35") (name "Net-(U52-OUT)") (class "Default")
      (node (ref "U52") (pin "3") (pinfunction "OUT_3") (pintype "output"))
      (node (ref "U77") (pin "1") (pinfunction "Y_1") (pintype "bidirectional"))
    )
    (net (code "36") (name "Net-(U53-OUT)") (class "Default")
      (node (ref "U53") (pin "3") (pinfunction "OUT_3") (pintype "output"))
      (node (ref "U76") (pin "1") (pinfunction "Y_1") (pintype "bidirectional"))
    )
    (net (code "37") (name "Net-(U54-OUT)") (class "Default")
      (node (ref "U54") (pin "3") (pinfunction "OUT_3") (pintype "output"))
      (node (ref "U75") (pin "1") (pinfunction "Y_1") (pintype "bidirectional"))
    )
    (net (code "38") (name "Net-(U55-OUT)") (class "Default")
      (node (ref "U55") (pin "3") (pinfunction "OUT_3") (pintype "output"))
      (node (ref "U74") (pin "1") (pinfunction "Y_1") (pintype "bidirectional"))
    )
    (net (code "39") (name "Net-(U56-OUT)") (class "Default")
      (node (ref "U56") (pin "3") (pinfunction "OUT_3") (pintype "output"))
      (node (ref "U73") (pin "1") (pinfunction "Y_1") (pintype "bidirectional"))
    )
    (net (code "40") (name "Net-(U57-OUT)") (class "Default")
      (node (ref "U57") (pin "3") (pinfunction "OUT_3") (pintype "output"))
      (node (ref "U72") (pin "1") (pinfunction "Y_1") (pintype "bidirectional"))
    )
    (net (code "41") (name "Net-(U58-OUT)") (class "Default")
      (node (ref "U58") (pin "3") (pinfunction "OUT_3") (pintype "output"))
      (node (ref "U71") (pin "1") (pinfunction "Y_1") (pintype "bidirectional"))
    )
    (net (code "42") (name "Net-(U59-OUT)") (class "Default")
      (node (ref "U59") (pin "3") (pinfunction "OUT_3") (pintype "output"))
      (node (ref "U70") (pin "1") (pinfunction "Y_1") (pintype "bidirectional"))
    )
    (net (code "43") (name "Net-(U60-OUT)") (class "Default")
      (node (ref "U60") (pin "3") (pinfunction "OUT_3") (pintype "output"))
      (node (ref "U69") (pin "1") (pinfunction "Y_1") (pintype "bidirectional"))
    )
    (net (code "44") (name "Net-(U61-OUT)") (class "Default")
      (node (ref "U61") (pin "3") (pinfunction "OUT_3") (pintype "output"))
      (node (ref "U68") (pin "1") (pinfunction "Y_1") (pintype "bidirectional"))
    )
    (net (code "45") (name "Net-(U62-OUT)") (class "Default")
      (node (ref "U62") (pin "3") (pinfunction "OUT_3") (pintype "output"))
      (node (ref "U67") (pin "1") (pinfunction "Y_1") (pintype "bidirectional"))
    )
    (net (code "46") (name "Net-(U63-OUT)") (class "Default")
      (node (ref "U63") (pin "3") (pinfunction "OUT_3") (pintype "output"))
      (node (ref "U66") (pin "1") (pinfunction "Y_1") (pintype "bidirectional"))
    )
    (net (code "47") (name "Net-(U64-OUT)") (class "Default")
      (node (ref "U64") (pin "3") (pinfunction "OUT_3") (pintype "output"))
      (node (ref "U65") (pin "1") (pinfunction "Y_1") (pintype "bidirectional"))
    )
    (net (code "48") (name "Net-(U100A-Y)") (class "Default")
      (node (ref "U100") (pin "1") (pinfunction "Y_1") (pintype "bidirectional"))
      (node (ref "U29") (pin "3") (pinfunction "OUT_3") (pintype "output"))
    )
    (net (code "49") (name "Net-(U101A-Y)") (class "Default")
      (node (ref "U101") (pin "1") (pinfunction "Y_1") (pintype "bidirectional"))
      (node (ref "U28") (pin "3") (pinfunction "OUT_3") (pintype "output"))
    )
    (net (code "50") (name "Net-(U102A-Y)") (class "Default")
      (node (ref "U102") (pin "1") (pinfunction "Y_1") (pintype "bidirectional"))
      (node (ref "U27") (pin "3") (pinfunction "OUT_3") (pintype "output"))
    )
    (net (code "51") (name "Net-(U103A-Y)") (class "Default")
      (node (ref "U103") (pin "1") (pinfunction "Y_1") (pintype "bidirectional"))
      (node (ref "U26") (pin "3") (pinfunction "OUT_3") (pintype "output"))
    )
    (net (code "52") (name "Net-(U104A-Y)") (class "Default")
      (node (ref "U104") (pin "1") (pinfunction "Y_1") (pintype "bidirectional"))
      (node (ref "U25") (pin "3") (pinfunction "OUT_3") (pintype "output"))
    )
    (net (code "53") (name "Net-(U105A-Y)") (class "Default")
      (node (ref "U105") (pin "1") (pinfunction "Y_1") (pintype "bidirectional"))
      (node (ref "U24") (pin "3") (pinfunction "OUT_3") (pintype "output"))
    )
    (net (code "54") (name "Net-(U106A-Y)") (class "Default")
      (node (ref "U106") (pin "1") (pinfunction "Y_1") (pintype "bidirectional"))
      (node (ref "U23") (pin "3") (pinfunction "OUT_3") (pintype "output"))
    )
    (net (code "55") (name "Net-(U107A-Y)") (class "Default")
      (node (ref "U107") (pin "1") (pinfunction "Y_1") (pintype "bidirectional"))
      (node (ref "U22") (pin "3") (pinfunction "OUT_3") (pintype "output"))
    )
    (net (code "56") (name "Net-(U108A-Y)") (class "Default")
      (node (ref "U108") (pin "1") (pinfunction "Y_1") (pintype "bidirectional"))
      (node (ref "U21") (pin "3") (pinfunction "OUT_3") (pintype "output"))
    )
    (net (code "57") (name "Net-(U109A-Y)") (class "Default")
      (node (ref "U109") (pin "1") (pinfunction "Y_1") (pintype "bidirectional"))
      (node (ref "U20") (pin "3") (pinfunction "OUT_3") (pintype "output"))
    )
    (net (code "58") (name "Net-(U110A-Y)") (class "Default")
      (node (ref "U110") (pin "1") (pinfunction "Y_1") (pintype "bidirectional"))
      (node (ref "U19") (pin "3") (pinfunction "OUT_3") (pintype "output"))
    )
    (net (code "59") (name "Net-(U111A-Y)") (class "Default")
      (node (ref "U111") (pin "1") (pinfunction "Y_1") (pintype "bidirectional"))
      (node (ref "U18") (pin "3") (pinfunction "OUT_3") (pintype "output"))
    )
    (net (code "60") (name "Net-(U112A-Y)") (class "Default")
      (node (ref "U112") (pin "1") (pinfunction "Y_1") (pintype "bidirectional"))
      (node (ref "U17") (pin "3") (pinfunction "OUT_3") (pintype "output"))
    )
    (net (code "61") (name "Net-(U113A-Y)") (class "Default")
      (node (ref "U113") (pin "1") (pinfunction "Y_1") (pintype "bidirectional"))
      (node (ref "U16") (pin "3") (pinfunction "OUT_3") (pintype "output"))
    )
    (net (code "62") (name "Net-(U114A-Y)") (class "Default")
      (node (ref "U114") (pin "1") (pinfunction "Y_1") (pintype "bidirectional"))
      (node (ref "U15") (pin "3") (pinfunction "OUT_3") (pintype "output"))
    )
    (net (code "63") (name "Net-(U115A-Y)") (class "Default")
      (node (ref "U115") (pin "1") (pinfunction "Y_1") (pintype "bidirectional"))
      (node (ref "U14") (pin "3") (pinfunction "OUT_3") (pintype "output"))
    )
    (net (code "64") (name "Net-(U116A-Y)") (class "Default")
      (node (ref "U116") (pin "1") (pinfunction "Y_1") (pintype "bidirectional"))
      (node (ref "U13") (pin "3") (pinfunction "OUT_3") (pintype "output"))
    )
    (net (code "65") (name "Net-(U117A-Y)") (class "Default")
      (node (ref "U117") (pin "1") (pinfunction "Y_1") (pintype "bidirectional"))
      (node (ref "U12") (pin "3") (pinfunction "OUT_3") (pintype "output"))
    )
    (net (code "66") (name "Net-(U120A-Y)") (class "Default")
      (node (ref "U120") (pin "1") (pinfunction "Y_1") (pintype "bidirectional"))
      (node (ref "U9") (pin "3") (pinfunction "OUT_3") (pintype "output"))
    )
    (net (code "67") (name "Net-(U121A-Y)") (class "Default")
      (node (ref "U121") (pin "1") (pinfunction "Y_1") (pintype "bidirectional"))
      (node (ref "U8") (pin "3") (pinfunction "OUT_3") (pintype "output"))
    )
    (net (code "68") (name "Net-(U122A-Y)") (class "Default")
      (node (ref "U122") (pin "1") (pinfunction "Y_1") (pintype "bidirectional"))
      (node (ref "U7") (pin "3") (pinfunction "OUT_3") (pintype "output"))
    )
    (net (code "69") (name "Net-(U123A-Y)") (class "Default")
      (node (ref "U123") (pin "1") (pinfunction "Y_1") (pintype "bidirectional"))
      (node (ref "U6") (pin "3") (pinfunction "OUT_3") (pintype "output"))
    )
    (net (code "70") (name "Net-(U124A-Y)") (class "Default")
      (node (ref "U124") (pin "1") (pinfunction "Y_1") (pintype "bidirectional"))
      (node (ref "U5") (pin "3") (pinfunction "OUT_3") (pintype "output"))
    )
    (net (code "71") (name "Net-(U125A-Y)") (class "Default")
      (node (ref "U125") (pin "1") (pinfunction "Y_1") (pintype "bidirectional"))
      (node (ref "U4") (pin "3") (pinfunction "OUT_3") (pintype "output"))
    )
    (net (code "72") (name "Net-(U126A-Y)") (class "Default")
      (node (ref "U126") (pin "1") (pinfunction "Y_1") (pintype "bidirectional"))
      (node (ref "U3") (pin "3") (pinfunction "OUT_3") (pintype "output"))
    )
    (net (code "73") (name "Net-(U127A-Y)") (class "Default")
      (node (ref "U127") (pin "1") (pinfunction "Y_1") (pintype "bidirectional"))
      (node (ref "U2") (pin "3") (pinfunction "OUT_3") (pintype "output"))
    )
    (net (code "74") (name "ROW0") (class "Default")
      (node (ref "U121") (pin "2") (pinfunction "Z_2") (pintype "bidirectional"))
      (node (ref "U122") (pin "2") (pinfunction "Z_2") (pintype "bidirectional"))
      (node (ref "U123") (pin "2") (pinfunction "Z_2") (pintype "bidirectional"))
      (node (ref "U124") (pin "2") (pinfunction "Z_2") (pintype "bidirectional"))
      (node (ref "U125") (pin "2") (pinfunction "Z_2") (pintype "bidirectional"))
      (node (ref "U126") (pin "2") (pinfunction "Z_2") (pintype "bidirectional"))
      (node (ref "U127") (pin "2") (pinfunction "Z_2") (pintype "bidirectional"))
      (node (ref "U128") (pin "2") (pinfunction "Z_2") (pintype "bidirectional"))
      (node (ref "X1") (pin "1") (pinfunction "1_1") (pintype "passive"))
    )
    (net (code "75") (name "ROW1") (class "Default")
      (node (ref "U113") (pin "2") (pinfunction "Z_2") (pintype "bidirectional"))
      (node (ref "U114") (pin "2") (pinfunction "Z_2") (pintype "bidirectional"))
      (node (ref "U115") (pin "2") (pinfunction "Z_2") (pintype "bidirectional"))
      (node (ref "U116") (pin "2") (pinfunction "Z_2") (pintype "bidirectional"))
      (node (ref "U117") (pin "2") (pinfunction "Z_2") (pintype "bidirectional"))
      (node (ref "U118") (pin "2") (pinfunction "Z_2") (pintype "bidirectional"))
      (node (ref "U119") (pin "2") (pinfunction "Z_2") (pintype "bidirectional"))
      (node (ref "U120") (pin "2") (pinfunction "Z_2") (pintype "bidirectional"))
      (node (ref "X1") (pin "2") (pinfunction "1_2") (pintype "passive"))
    )
    (net (code "76") (name "ROW2") (class "Default")
      (node (ref "U105") (pin "2") (pinfunction "Z_2") (pintype "bidirectional"))
      (node (ref "U106") (pin "2") (pinfunction "Z_2") (pintype "bidirectional"))
      (node (ref "U107") (pin "2") (pinfunction "Z_2") (pintype "bidirectional"))
      (node (ref "U108") (pin "2") (pinfunction "Z_2") (pintype "bidirectional"))
      (node (ref "U109") (pin "2") (pinfunction "Z_2") (pintype "bidirectional"))
      (node (ref "U110") (pin "2") (pinfunction "Z_2") (pintype "bidirectional"))
      (node (ref "U111") (pin "2") (pinfunction "Z_2") (pintype "bidirectional"))
      (node (ref "U112") (pin "2") (pinfunction "Z_2") (pintype "bidirectional"))
      (node (ref "X1") (pin "3") (pinfunction "1_3") (pintype "passive"))
    )
    (net (code "77") (name "ROW3") (class "Default")
      (node (ref "U100") (pin "2") (pinfunction "Z_2") (pintype "bidirectional"))
      (node (ref "U101") (pin "2") (pinfunction "Z_2") (pintype "bidirectional"))
      (node (ref "U102") (pin "2") (pinfunction "Z_2") (pintype "bidirectional"))
      (node (ref "U103") (pin "2") (pinfunction "Z_2") (pintype "bidirectional"))
      (node (ref "U104") (pin "2") (pinfunction "Z_2") (pintype "bidirectional"))
      (node (ref "U97") (pin "2") (pinfunction "Z_2") (pintype "bidirectional"))
      (node (ref "U98") (pin "2") (pinfunction "Z_2") (pintype "bidirectional"))
      (node (ref "U99") (pin "2") (pinfunction "Z_2") (pintype "bidirectional"))
      (node (ref "X1") (pin "4") (pinfunction "1_4") (pintype "passive"))
    )
    (net (code "78") (name "ROW4") (class "Default")
      (node (ref "U89") (pin "2") (pinfunction "Z_2") (pintype "bidirectional"))
      (node (ref "U90") (pin "2") (pinfunction "Z_2") (pintype "bidirectional"))
      (node (ref "U91") (pin "2") (pinfunction "Z_2") (pintype "bidirectional"))
      (node (ref "U92") (pin "2") (pinfunction "Z_2") (pintype "bidirectional"))
      (node (ref "U93") (pin "2") (pinfunction "Z_2") (pintype "bidirectional"))
      (node (ref "U94") (pin "2") (pinfunction "Z_2") (pintype "bidirectional"))
      (node (ref "U95") (pin "2") (pinfunction "Z_2") (pintype "bidirectional"))
      (node (ref "U96") (pin "2") (pinfunction "Z_2") (pintype "bidirectional"))
      (node (ref "X1") (pin "5") (pinfunction "1_5") (pintype "passive"))
    )
    (net (code "79") (name "ROW5") (class "Default")
      (node (ref "U81") (pin "2") (pinfunction "Z_2") (pintype "bidirectional"))
      (node (ref "U82") (pin "2") (pinfunction "Z_2") (pintype "bidirectional"))
      (node (ref "U83") (pin "2") (pinfunction "Z_2") (pintype "bidirectional"))
      (node (ref "U84") (pin "2") (pinfunction "Z_2") (pintype "bidirectional"))
      (node (ref "U85") (pin "2") (pinfunction "Z_2") (pintype "bidirectional"))
      (node (ref "U86") (pin "2") (pinfunction "Z_2") (pintype "bidirectional"))
      (node (ref "U87") (pin "2") (pinfunction "Z_2") (pintype "bidirectional"))
      (node (ref "U88") (pin "2") (pinfunction "Z_2") (pintype "bidirectional"))
      (node (ref "X1") (pin "6") (pinfunction "1_6") (pintype "passive"))
    )
    (net (code "80") (name "ROW6") (class "Default")
      (node (ref "U73") (pin "2") (pinfunction "Z_2") (pintype "bidirectional"))
      (node (ref "U74") (pin "2") (pinfunction "Z_2") (pintype "bidirectional"))
      (node (ref "U75") (pin "2") (pinfunction "Z_2") (pintype "bidirectional"))
      (node (ref "U76") (pin "2") (pinfunction "Z_2") (pintype "bidirectional"))
      (node (ref "U77") (pin "2") (pinfunction "Z_2") (pintype "bidirectional"))
      (node (ref "U78") (pin "2") (pinfunction "Z_2") (pintype "bidirectional"))
      (node (ref "U79") (pin "2") (pinfunction "Z_2") (pintype "bidirectional"))
      (node (ref "U80") (pin "2") (pinfunction "Z_2") (pintype "bidirectional"))
      (node (ref "X1") (pin "7") (pinfunction "1_7") (pintype "passive"))
    )
    (net (code "81") (name "ROW7") (class "Default")
      (node (ref "U65") (pin "2") (pinfunction "Z_2") (pintype "bidirectional"))
      (node (ref "U66") (pin "2") (pinfunction "Z_2") (pintype "bidirectional"))
      (node (ref "U67") (pin "2") (pinfunction "Z_2") (pintype "bidirectional"))
      (node (ref "U68") (pin "2") (pinfunction "Z_2") (pintype "bidirectional"))
      (node (ref "U69") (pin "2") (pinfunction "Z_2") (pintype "bidirectional"))
      (node (ref "U70") (pin "2") (pinfunction "Z_2") (pintype "bidirectional"))
      (node (ref "U71") (pin "2") (pinfunction "Z_2") (pintype "bidirectional"))
      (node (ref "U72") (pin "2") (pinfunction "Z_2") (pintype "bidirectional"))
      (node (ref "X1") (pin "8") (pinfunction "1_8") (pintype "passive"))
    )
    (net (code "82") (name "VCC") (class "Default")
      (node (ref "C1") (pin "1") (pinfunction "1_1") (pintype "passive"))
      (node (ref "C10") (pin "1") (pinfunction "1_1") (pintype "passive"))
      (node (ref "C11") (pin "1") (pinfunction "1_1") (pintype "passive"))
      (node (ref "C12") (pin "1") (pinfunction "1_1") (pintype "passive"))
      (node (ref "C13") (pin "1") (pinfunction "1_1") (pintype "passive"))
      (node (ref "C14") (pin "1") (pinfunction "1_1") (pintype "passive"))
      (node (ref "C15") (pin "1") (pinfunction "1_1") (pintype "passive"))
      (node (ref "C16") (pin "1") (pinfunction "1_1") (pintype "passive"))
      (node (ref "C17") (pin "1") (pinfunction "1_1") (pintype "passive"))
      (node (ref "C18") (pin "1") (pinfunction "1_1") (pintype "passive"))
      (node (ref "C19") (pin "1") (pinfunction "1_1") (pintype "passive"))
      (node (ref "C2") (pin "1") (pinfunction "1_1") (pintype "passive"))
      (node (ref "C20") (pin "1") (pinfunction "1_1") (pintype "passive"))
      (node (ref "C21") (pin "1") (pinfunction "1_1") (pintype "passive"))
      (node (ref "C22") (pin "1") (pinfunction "1_1") (pintype "passive"))
      (node (ref "C23") (pin "1") (pinfunction "1_1") (pintype "passive"))
      (node (ref "C24") (pin "1") (pinfunction "1_1") (pintype "passive"))
      (node (ref "C25") (pin "1") (pinfunction "1_1") (pintype "passive"))
      (node (ref "C26") (pin "1") (pinfunction "1_1") (pintype "passive"))
      (node (ref "C27") (pin "1") (pinfunction "1_1") (pintype "passive"))
      (node (ref "C28") (pin "1") (pinfunction "1_1") (pintype "passive"))
      (node (ref "C29") (pin "1") (pinfunction "1_1") (pintype "passive"))
      (node (ref "C3") (pin "1") (pinfunction "1_1") (pintype "passive"))
      (node (ref "C30") (pin "1") (pinfunction "1_1") (pintype "passive"))
      (node (ref "C31") (pin "1") (pinfunction "1_1") (pintype "passive"))
      (node (ref "C32") (pin "1") (pinfunction "1_1") (pintype "passive"))
      (node (ref "C33") (pin "1") (pinfunction "1_1") (pintype "passive"))
      (node (ref "C34") (pin "1") (pinfunction "1_1") (pintype "passive"))
      (node (ref "C35") (pin "1") (pinfunction "1_1") (pintype "passive"))
      (node (ref "C36") (pin "1") (pinfunction "1_1") (pintype "passive"))
      (node (ref "C37") (pin "1") (pinfunction "1_1") (pintype "passive"))
      (node (ref "C38") (pin "1") (pinfunction "1_1") (pintype "passive"))
      (node (ref "C39") (pin "1") (pinfunction "1_1") (pintype "passive"))
      (node (ref "C4") (pin "1") (pinfunction "1_1") (pintype "passive"))
      (node (ref "C40") (pin "1") (pinfunction "1_1") (pintype "passive"))
      (node (ref "C41") (pin "1") (pinfunction "1_1") (pintype "passive"))
      (node (ref "C42") (pin "1") (pinfunction "1_1") (pintype "passive"))
      (node (ref "C43") (pin "1") (pinfunction "1_1") (pintype "passive"))
      (node (ref "C44") (pin "1") (pinfunction "1_1") (pintype "passive"))
      (node (ref "C45") (pin "1") (pinfunction "1_1") (pintype "passive"))
      (node (ref "C46") (pin "1") (pinfunction "1_1") (pintype "passive"))
      (node (ref "C47") (pin "1") (pinfunction "1_1") (pintype "passive"))
      (node (ref "C48") (pin "1") (pinfunction "1_1") (pintype "passive"))
      (node (ref "C49") (pin "1") (pinfunction "1_1") (pintype "passive"))
      (node (ref "C5") (pin "1") (pinfunction "1_1") (pintype "passive"))
      (node (ref "C50") (pin "1") (pinfunction "1_1") (pintype "passive"))
      (node (ref "C51") (pin "1") (pinfunction "1_1") (pintype "passive"))
      (node (ref "C52") (pin "1") (pinfunction "1_1") (pintype "passive"))
      (node (ref "C53") (pin "1") (pinfunction "1_1") (pintype "passive"))
      (node (ref "C54") (pin "1") (pinfunction "1_1") (pintype "passive"))
      (node (ref "C55") (pin "1") (pinfunction "1_1") (pintype "passive"))
      (node (ref "C56") (pin "1") (pinfunction "1_1") (pintype "passive"))
      (node (ref "C6") (pin "1") (pinfunction "1_1") (pintype "passive"))
      (node (ref "C7") (pin "1") (pinfunction "1_1") (pintype "passive"))
      (node (ref "C8") (pin "1") (pinfunction "1_1") (pintype "passive"))
      (node (ref "C9") (pin "1") (pinfunction "1_1") (pintype "passive"))
      (node (ref "U1") (pin "1") (pinfunction "VCC_1") (pintype "power_in"))
      (node (ref "U10") (pin "1") (pinfunction "VCC_1") (pintype "power_in"))
      (node (ref "U11") (pin "1") (pinfunction "VCC_1") (pintype "power_in"))
      (node (ref "U12") (pin "1") (pinfunction "VCC_1") (pintype "power_in"))
      (node (ref "U13") (pin "1") (pinfunction "VCC_1") (pintype "power_in"))
      (node (ref "U14") (pin "1") (pinfunction "VCC_1") (pintype "power_in"))
      (node (ref "U15") (pin "1") (pinfunction "VCC_1") (pintype "power_in"))
      (node (ref "U16") (pin "1") (pinfunction "VCC_1") (pintype "power_in"))
      (node (ref "U17") (pin "1") (pinfunction "VCC_1") (pintype "power_in"))
      (node (ref "U18") (pin "1") (pinfunction "VCC_1") (pintype "power_in"))
      (node (ref "U19") (pin "1") (pinfunction "VCC_1") (pintype "power_in"))
      (node (ref "U2") (pin "1") (pinfunction "VCC_1") (pintype "power_in"))
      (node (ref "U20") (pin "1") (pinfunction "VCC_1") (pintype "power_in"))
      (node (ref "U21") (pin "1") (pinfunction "VCC_1") (pintype "power_in"))
      (node (ref "U22") (pin "1") (pinfunction "VCC_1") (pintype "power_in"))
      (node (ref "U23") (pin "1") (pinfunction "VCC_1") (pintype "power_in"))
      (node (ref "U24") (pin "1") (pinfunction "VCC_1") (pintype "power_in"))
      (node (ref "U25") (pin "1") (pinfunction "VCC_1") (pintype "power_in"))
      (node (ref "U26") (pin "1") (pinfunction "VCC_1") (pintype "power_in"))
      (node (ref "U27") (pin "1") (pinfunction "VCC_1") (pintype "power_in"))
      (node (ref "U28") (pin "1") (pinfunction "VCC_1") (pintype "power_in"))
      (node (ref "U29") (pin "1") (pinfunction "VCC_1") (pintype "power_in"))
      (node (ref "U3") (pin "1") (pinfunction "VCC_1") (pintype "power_in"))
      (node (ref "U30") (pin "1") (pinfunction "VCC_1") (pintype "power_in"))
      (node (ref "U31") (pin "1") (pinfunction "VCC_1") (pintype "power_in"))
      (node (ref "U32") (pin "1") (pinfunction "VCC_1") (pintype "power_in"))
      (node (ref "U33") (pin "1") (pinfunction "VCC_1") (pintype "power_in"))
      (node (ref "U34") (pin "1") (pinfunction "VCC_1") (pintype "power_in"))
      (node (ref "U35") (pin "1") (pinfunction "VCC_1") (pintype "power_in"))
      (node (ref "U36") (pin "1") (pinfunction "VCC_1") (pintype "power_in"))
      (node (ref "U37") (pin "1") (pinfunction "VCC_1") (pintype "power_in"))
      (node (ref "U38") (pin "1") (pinfunction "VCC_1") (pintype "power_in"))
      (node (ref "U39") (pin "1") (pinfunction "VCC_1") (pintype "power_in"))
      (node (ref "U4") (pin "1") (pinfunction "VCC_1") (pintype "power_in"))
      (node (ref "U40") (pin "1") (pinfunction "VCC_1") (pintype "power_in"))
      (node (ref "U41") (pin "1") (pinfunction "VCC_1") (pintype "power_in"))
      (node (ref "U42") (pin "1") (pinfunction "VCC_1") (pintype "power_in"))
      (node (ref "U43") (pin "1") (pinfunction "VCC_1") (pintype "power_in"))
      (node (ref "U44") (pin "1") (pinfunction "VCC_1") (pintype "power_in"))
      (node (ref "U45") (pin "1") (pinfunction "VCC_1") (pintype "power_in"))
      (node (ref "U46") (pin "1") (pinfunction "VCC_1") (pintype "power_in"))
      (node (ref "U47") (pin "1") (pinfunction "VCC_1") (pintype "power_in"))
      (node (ref "U48") (pin "1") (pinfunction "VCC_1") (pintype "power_in"))
      (node (ref "U49") (pin "1") (pinfunction "VCC_1") (pintype "power_in"))
      (node (ref "U5") (pin "1") (pinfunction "VCC_1") (pintype "power_in"))
      (node (ref "U50") (pin "1") (pinfunction "VCC_1") (pintype "power_in"))
      (node (ref "U51") (pin "1") (pinfunction "VCC_1") (pintype "power_in"))
      (node (ref "U52") (pin "1") (pinfunction "VCC_1") (pintype "power_in"))
      (node (ref "U53") (pin "1") (pinfunction "VCC_1") (pintype "power_in"))
      (node (ref "U54") (pin "1") (pinfunction "VCC_1") (pintype "power_in"))
      (node (ref "U55") (pin "1") (pinfunction "VCC_1") (pintype "power_in"))
      (node (ref "U56") (pin "1") (pinfunction "VCC_1") (pintype "power_in"))
      (node (ref "U57") (pin "1") (pinfunction "VCC_1") (pintype "power_in"))
      (node (ref "U58") (pin "1") (pinfunction "VCC_1") (pintype "power_in"))
      (node (ref "U59") (pin "1") (pinfunction "VCC_1") (pintype "power_in"))
      (node (ref "U6") (pin "1") (pinfunction "VCC_1") (pintype "power_in"))
      (node (ref "U60") (pin "1") (pinfunction "VCC_1") (pintype "power_in"))
      (node (ref "U61") (pin "1") (pinfunction "VCC_1") (pintype "power_in"))
      (node (ref "U62") (pin "1") (pinfunction "VCC_1") (pintype "power_in"))
      (node (ref "U63") (pin "1") (pinfunction "VCC_1") (pintype "power_in"))
      (node (ref "U64") (pin "1") (pinfunction "VCC_1") (pintype "power_in"))
      (node (ref "U7") (pin "1") (pinfunction "VCC_1") (pintype "power_in"))
      (node (ref "U8") (pin "1") (pinfunction "VCC_1") (pintype "power_in"))
      (node (ref "U9") (pin "1") (pinfunction "VCC_1") (pintype "power_in"))
      (node (ref "X1") (pin "11") (pinfunction "1_11") (pintype "passive"))
      (node (ref "X1") (pin "12") (pinfunction "1_12") (pintype "passive"))
    )
  )
)
